# SAMD21.net
KiCad netlist of a schematic drawn in Altium Designer
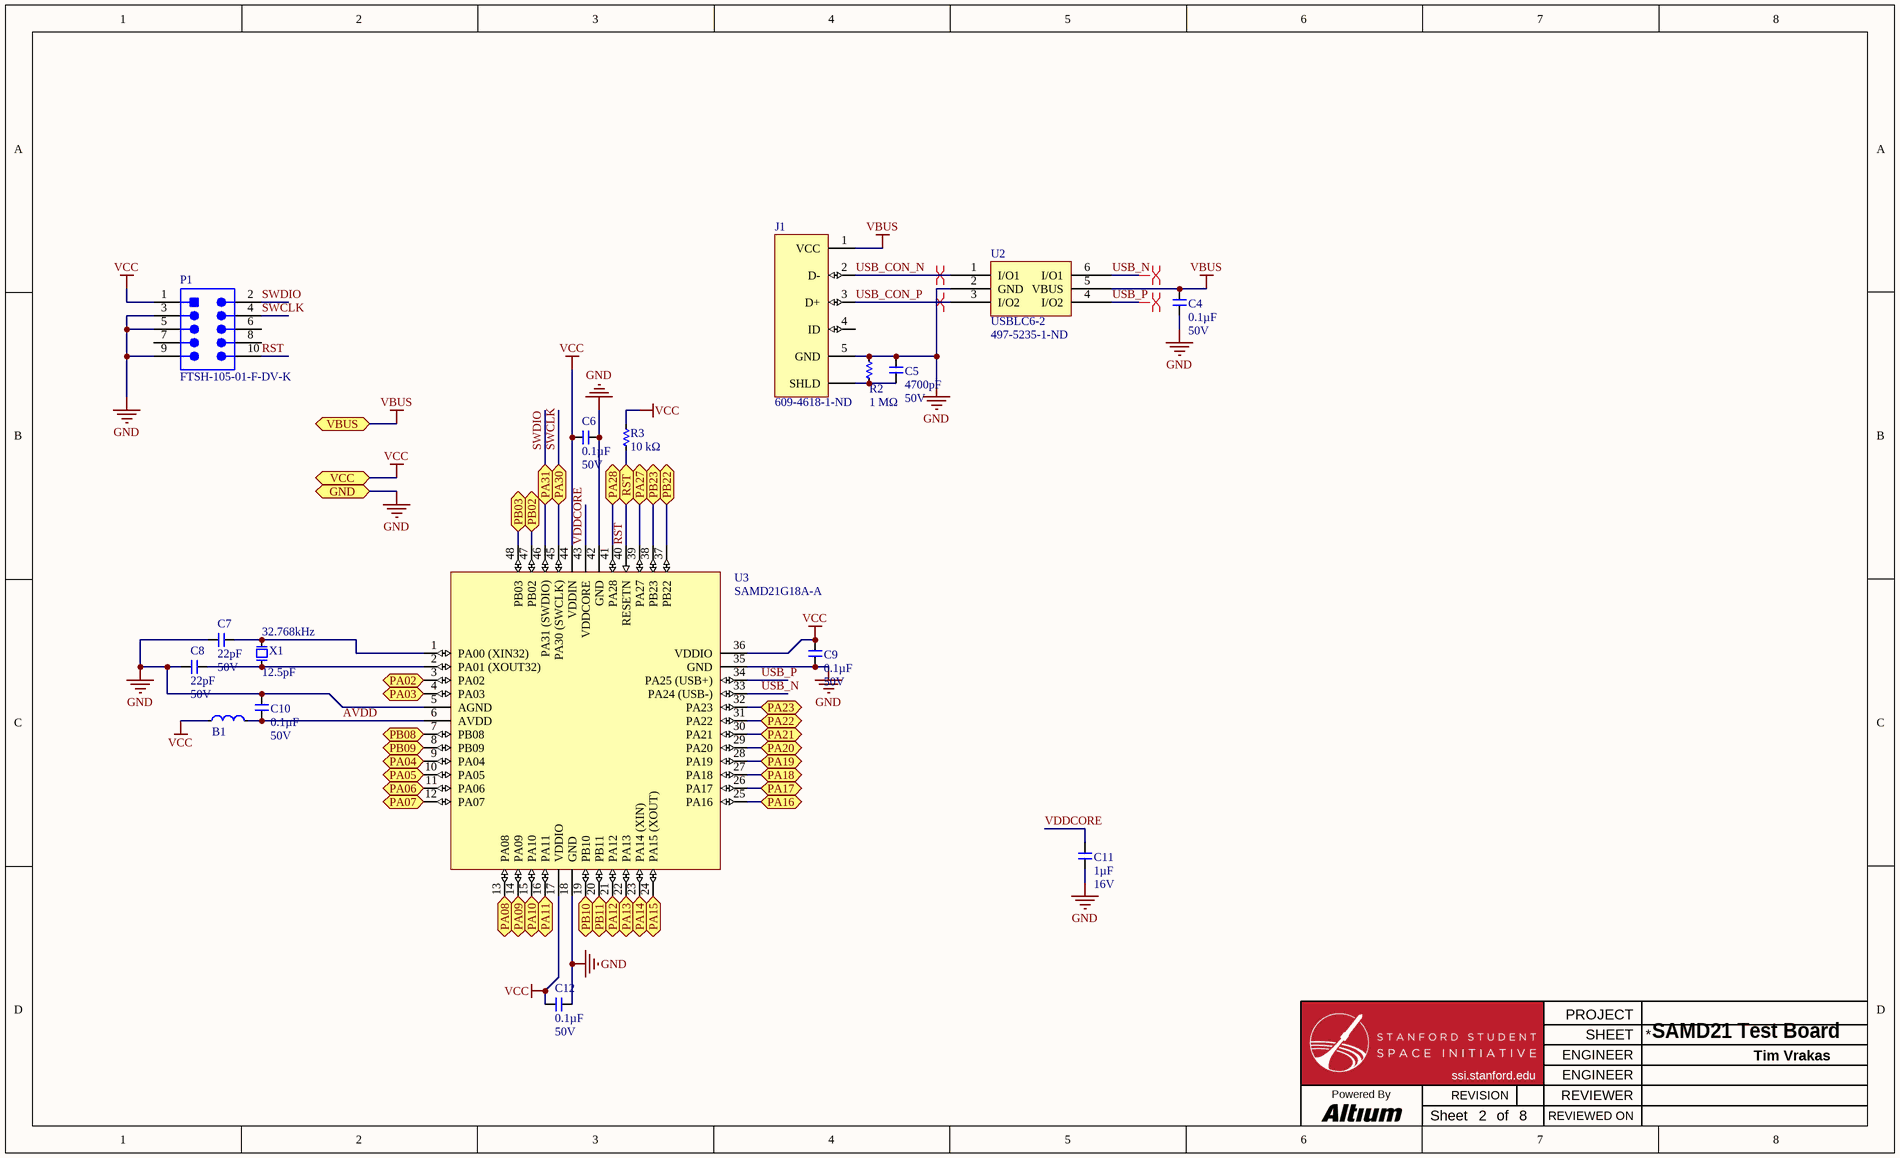
[diagram p0: SAMD21.SchDoc]

(export (version "E")
  (design (tool "Eeschema 10.0.6"))
  (components
    (comp (ref "B1")
      (value "FB_1608")
      (footprint "R0603")
      (description "FERRITE BEAD 600 OHM 300mA")
      (fields
        (field (name "MANUFACTURER") "Taiyo Yuden")
        (field (name "MANUFACTURER PART NUMBER") "BK1608HW601-T")
      )
      (libsource (lib "SSI") (part "FB_1608"))
    )
    (comp (ref "C4")
      (value "__template_cap")
      (footprint "C0603")
      (description "CAP CER 0603 0.1µF X7R 50V 10%")
      (fields
        (field (name "CAPACITANCE (SHORTHAND)") "0.1µF")
        (field (name "RATED VOLTAGE") "50V")
        (field (name "MANUFACTURER") "Murata Electronics North America")
      )
      (libsource (lib "passives") (part "__template_cap"))
    )
    (comp (ref "C5")
      (value "__template_cap")
      (footprint "C0603")
      (description "CAP CER 0603 4700pF X7R 50V 10%")
      (fields
        (field (name "CAPACITANCE (SHORTHAND)") "4700pF")
        (field (name "RATED VOLTAGE") "50V")
        (field (name "MANUFACTURER") "Murata Electronics North America")
      )
      (libsource (lib "passives") (part "__template_cap"))
    )
    (comp (ref "C6")
      (value "__template_cap")
      (footprint "C0603")
      (description "CAP CER 0603 0.1µF X7R 50V 10%")
      (fields
        (field (name "CAPACITANCE (SHORTHAND)") "0.1µF")
        (field (name "RATED VOLTAGE") "50V")
        (field (name "MANUFACTURER") "Murata Electronics North America")
      )
      (libsource (lib "passives") (part "__template_cap"))
    )
    (comp (ref "C7")
      (value "__template_cap")
      (footprint "C0603")
      (description "CAP CER 22PF 50V C0G/NP0 0603")
      (fields
        (field (name "CAPACITANCE (SHORTHAND)") "22pF")
        (field (name "RATED VOLTAGE") "50V")
        (field (name "MANUFACTURER") "Murata Electronics North America")
      )
      (libsource (lib "passives") (part "__template_cap"))
    )
    (comp (ref "C8")
      (value "__template_cap")
      (footprint "C0603")
      (description "CAP CER 22PF 50V C0G/NP0 0603")
      (fields
        (field (name "CAPACITANCE (SHORTHAND)") "22pF")
        (field (name "RATED VOLTAGE") "50V")
        (field (name "MANUFACTURER") "Murata Electronics North America")
      )
      (libsource (lib "passives") (part "__template_cap"))
    )
    (comp (ref "C9")
      (value "__template_cap")
      (footprint "C0603")
      (description "CAP CER 0603 0.1µF X7R 50V 10%")
      (fields
        (field (name "CAPACITANCE (SHORTHAND)") "0.1µF")
        (field (name "RATED VOLTAGE") "50V")
        (field (name "MANUFACTURER") "Murata Electronics North America")
      )
      (libsource (lib "passives") (part "__template_cap"))
    )
    (comp (ref "C10")
      (value "__template_cap")
      (footprint "C0603")
      (description "CAP CER 0603 0.1µF X7R 50V 10%")
      (fields
        (field (name "CAPACITANCE (SHORTHAND)") "0.1µF")
        (field (name "RATED VOLTAGE") "50V")
        (field (name "MANUFACTURER") "Murata Electronics North America")
      )
      (libsource (lib "passives") (part "__template_cap"))
    )
    (comp (ref "C11")
      (value "__template_cap")
      (footprint "C0603")
      (description "CAP CER 0603 1µF X7R 16V 10%")
      (fields
        (field (name "CAPACITANCE (SHORTHAND)") "1µF")
        (field (name "RATED VOLTAGE") "16V")
        (field (name "MANUFACTURER") "Murata Electronics North America")
      )
      (libsource (lib "passives") (part "__template_cap"))
    )
    (comp (ref "C12")
      (value "__template_cap")
      (footprint "C0603")
      (description "CAP CER 0603 0.1µF X7R 50V 10%")
      (fields
        (field (name "CAPACITANCE (SHORTHAND)") "0.1µF")
        (field (name "RATED VOLTAGE") "50V")
        (field (name "MANUFACTURER") "Murata Electronics North America")
      )
      (libsource (lib "passives") (part "__template_cap"))
    )
    (comp (ref "J1")
      (value "CONN_USB_MICROB_SMD_TH_R/A")
      (footprint "CONN_USBMICROB_10118194-0001LF")
      (description "CONN RCPT USB2.0 MICRO B SMD R/A")
      (fields
        (field (name "MANUFACTURER") "Amphenol FCI")
        (field (name "MANUFACTURER PART NUMBER") "10118194-0001LF")
        (field (name "SUPPLIER PART NUMBER 1") "609-4618-1-ND")
      )
      (libsource (lib "SSI") (part "CONN_USB_MICROB_SMD_TH_R/A"))
    )
    (comp (ref "P1")
      (value "FTSH-105-01-F-DV-K")
      (footprint "SMTC-FTSH-105-01-L-DV-K_V")
      (description "Male Header, Pitch 1.27 mm, 2 x 5 Position, Height 6.12 mm, RoHS, Tube")
      (fields (field (name "MANUFACTURER") "Samtec"))
      (libsource (lib "Altium Content Vault") (part "CN-2P-M-R10"))
    )
    (comp (ref "R2")
      (value "__template_resistor")
      (footprint "R0603")
      (description "RES SMD 1M OHM 1% 1/10W 0603")
      (fields
        (field (name "RESISTANCE") "1 MΩ")
        (field (name "MANUFACTURER PART NUMBER") "RC0603FR-071ML")
        (field (name "MANUFACTURER") "Yageo")
      )
      (libsource (lib "passives") (part "__template_resistor"))
    )
    (comp (ref "R3")
      (value "__template_resistor")
      (footprint "R0603")
      (description "RES SMD 10K OHM 1% 1/10W 0603")
      (fields
        (field (name "RESISTANCE") "10 kΩ")
        (field (name "MANUFACTURER PART NUMBER") "RC0603FR-0710KL")
        (field (name "MANUFACTURER") "Yageo")
      )
      (libsource (lib "passives") (part "__template_resistor"))
    )
    (comp (ref "U2")
      (value "USBLC6-2")
      (footprint "6SOT23")
      (fields
        (field (name "MANUFACTURER") "STMicroelectronics")
        (field (name "MANUFACTURER PART NUMBER") "USBLC6-2SC6")
        (field (name "SUPPLIER PART NUMBER 1") "497-5235-1-ND")
      )
      (libsource (lib "SSI") (part "USBLC6-2"))
    )
    (comp (ref "U3")
      (value "SAMD21G18A-A")
      (footprint "SAMD21 TQFP-48")
      (description "48Mhz Atmel SAM ARM Cortex M0+")
      (libsource (lib "SSI") (part "SAMD21G18A-A"))
    )
    (comp (ref "X1")
      (value "XTAL_9HT10-32.768KEZF-T")
      (footprint "XTAL_TXC_9HT10")
      (description "CRYSTAL 32.768 KHZ 12.5 PF SMD")
      (fields
        (field (name "MANUFACTURER") "TXC CORPORATION")
        (field (name "MANUFACTURER PART NUMBER") "9HT10-32.768KEZF-T")
        (field (name "FREQUENCY") "32.768kHz")
        (field (name "LOAD CAPACITANCE") "12.5pF")
      )
      (libsource (lib "SSI") (part "XTAL_9HT10-32.768KEZF-T"))
    )
  )
  (nets
    (net (code "1") (name "/AVDD") (class "Default")
      (node (ref "B1") (pin "2") (pinfunction "2_2") (pintype "passive"))
      (node (ref "C10") (pin "2") (pintype "passive"))
      (node (ref "U3") (pin "6") (pinfunction "AVDD_6") (pintype "power_in"))
    )
    (net (code "2") (name "/PA02") (class "Default")
      (node (ref "U3") (pin "3") (pinfunction "PA02_3") (pintype "bidirectional"))
    )
    (net (code "3") (name "/PA03") (class "Default")
      (node (ref "U3") (pin "4") (pinfunction "PA03_4") (pintype "bidirectional"))
    )
    (net (code "4") (name "/PA04") (class "Default")
      (node (ref "U3") (pin "9") (pinfunction "PA04_9") (pintype "bidirectional"))
    )
    (net (code "5") (name "/PA05") (class "Default")
      (node (ref "U3") (pin "10") (pinfunction "PA05_10") (pintype "bidirectional"))
    )
    (net (code "6") (name "/PA06") (class "Default")
      (node (ref "U3") (pin "11") (pinfunction "PA06_11") (pintype "bidirectional"))
    )
    (net (code "7") (name "/PA07") (class "Default")
      (node (ref "U3") (pin "12") (pinfunction "PA07_12") (pintype "bidirectional"))
    )
    (net (code "8") (name "/PA08") (class "Default")
      (node (ref "U3") (pin "13") (pinfunction "PA08_13") (pintype "bidirectional"))
    )
    (net (code "9") (name "/PA09") (class "Default")
      (node (ref "U3") (pin "14") (pinfunction "PA09_14") (pintype "bidirectional"))
    )
    (net (code "10") (name "/PA10") (class "Default")
      (node (ref "U3") (pin "15") (pinfunction "PA10_15") (pintype "bidirectional"))
    )
    (net (code "11") (name "/PA11") (class "Default")
      (node (ref "U3") (pin "16") (pinfunction "PA11_16") (pintype "bidirectional"))
    )
    (net (code "12") (name "/PA12") (class "Default")
      (node (ref "U3") (pin "21") (pinfunction "PA12_21") (pintype "bidirectional"))
    )
    (net (code "13") (name "/PA13") (class "Default")
      (node (ref "U3") (pin "22") (pinfunction "PA13_22") (pintype "bidirectional"))
    )
    (net (code "14") (name "/PA14") (class "Default")
      (node (ref "U3") (pin "23") (pinfunction "PA14_(XIN)_23") (pintype "bidirectional"))
    )
    (net (code "15") (name "/PA15") (class "Default")
      (node (ref "U3") (pin "24") (pinfunction "PA15_(XOUT)_24") (pintype "bidirectional"))
    )
    (net (code "16") (name "/PA16") (class "Default")
      (node (ref "U3") (pin "25") (pinfunction "PA16_25") (pintype "bidirectional"))
    )
    (net (code "17") (name "/PA17") (class "Default")
      (node (ref "U3") (pin "26") (pinfunction "PA17_26") (pintype "bidirectional"))
    )
    (net (code "18") (name "/PA18") (class "Default")
      (node (ref "U3") (pin "27") (pinfunction "PA18_27") (pintype "bidirectional"))
    )
    (net (code "19") (name "/PA19") (class "Default")
      (node (ref "U3") (pin "28") (pinfunction "PA19_28") (pintype "bidirectional"))
    )
    (net (code "20") (name "/PA20") (class "Default")
      (node (ref "U3") (pin "29") (pinfunction "PA20_29") (pintype "bidirectional"))
    )
    (net (code "21") (name "/PA21") (class "Default")
      (node (ref "U3") (pin "30") (pinfunction "PA21_30") (pintype "bidirectional"))
    )
    (net (code "22") (name "/PA22") (class "Default")
      (node (ref "U3") (pin "31") (pinfunction "PA22_31") (pintype "bidirectional"))
    )
    (net (code "23") (name "/PA23") (class "Default")
      (node (ref "U3") (pin "32") (pinfunction "PA23_32") (pintype "bidirectional"))
    )
    (net (code "24") (name "/PA27") (class "Default")
      (node (ref "U3") (pin "39") (pinfunction "PA27_39") (pintype "bidirectional"))
    )
    (net (code "25") (name "/PA28") (class "Default")
      (node (ref "U3") (pin "41") (pinfunction "PA28_41") (pintype "bidirectional"))
    )
    (net (code "26") (name "/PB02") (class "Default")
      (node (ref "U3") (pin "47") (pinfunction "PB02_47") (pintype "bidirectional"))
    )
    (net (code "27") (name "/PB03") (class "Default")
      (node (ref "U3") (pin "48") (pinfunction "PB03_48") (pintype "bidirectional"))
    )
    (net (code "28") (name "/PB08") (class "Default")
      (node (ref "U3") (pin "7") (pinfunction "PB08_7") (pintype "bidirectional"))
    )
    (net (code "29") (name "/PB09") (class "Default")
      (node (ref "U3") (pin "8") (pinfunction "PB09_8") (pintype "bidirectional"))
    )
    (net (code "30") (name "/PB10") (class "Default")
      (node (ref "U3") (pin "19") (pinfunction "PB10_19") (pintype "bidirectional"))
    )
    (net (code "31") (name "/PB11") (class "Default")
      (node (ref "U3") (pin "20") (pinfunction "PB11_20") (pintype "bidirectional"))
    )
    (net (code "32") (name "/PB22") (class "Default")
      (node (ref "U3") (pin "37") (pinfunction "PB22_37") (pintype "bidirectional"))
    )
    (net (code "33") (name "/PB23") (class "Default")
      (node (ref "U3") (pin "38") (pinfunction "PB23_38") (pintype "bidirectional"))
    )
    (net (code "34") (name "/RST") (class "Default")
      (node (ref "P1") (pin "10") (pinfunction "10_10") (pintype "passive"))
      (node (ref "R3") (pin "1") (pintype "passive"))
      (node (ref "U3") (pin "40") (pinfunction "RESETN_40") (pintype "input"))
    )
    (net (code "35") (name "/SWCLK") (class "Default")
      (node (ref "P1") (pin "4") (pinfunction "4_4") (pintype "passive"))
      (node (ref "U3") (pin "45") (pinfunction "PA30_(SWCLK)_45") (pintype "bidirectional"))
    )
    (net (code "36") (name "/SWDIO") (class "Default")
      (node (ref "P1") (pin "2") (pinfunction "2_2") (pintype "passive"))
      (node (ref "U3") (pin "46") (pinfunction "PA31_(SWDIO)_46") (pintype "bidirectional"))
    )
    (net (code "37") (name "/USB_CON_N") (class "Default")
      (node (ref "J1") (pin "2") (pinfunction "D-_2") (pintype "bidirectional"))
      (node (ref "U2") (pin "1") (pinfunction "I/O1_1") (pintype "passive"))
    )
    (net (code "38") (name "/USB_CON_P") (class "Default")
      (node (ref "J1") (pin "3") (pinfunction "D+_3") (pintype "bidirectional"))
      (node (ref "U2") (pin "3") (pinfunction "I/O2_3") (pintype "passive"))
    )
    (net (code "39") (name "/USB_N") (class "Default")
      (node (ref "U2") (pin "6") (pinfunction "I/O1_6") (pintype "passive"))
      (node (ref "U3") (pin "33") (pinfunction "PA24_(USB-)_33") (pintype "bidirectional"))
    )
    (net (code "40") (name "/USB_P") (class "Default")
      (node (ref "U2") (pin "4") (pinfunction "I/O2_4") (pintype "passive"))
      (node (ref "U3") (pin "34") (pinfunction "PA25_(USB+)_34") (pintype "bidirectional"))
    )
    (net (code "41") (name "/VDDCORE") (class "Default")
      (node (ref "C11") (pin "1") (pintype "passive"))
      (node (ref "U3") (pin "43") (pinfunction "VDDCORE_43") (pintype "power_in"))
    )
    (net (code "42") (name "GND") (class "Default")
      (node (ref "C10") (pin "1") (pintype "passive"))
      (node (ref "C11") (pin "2") (pintype "passive"))
      (node (ref "C12") (pin "2") (pintype "passive"))
      (node (ref "C4") (pin "2") (pintype "passive"))
      (node (ref "C5") (pin "1") (pintype "passive"))
      (node (ref "C6") (pin "2") (pintype "passive"))
      (node (ref "C7") (pin "1") (pintype "passive"))
      (node (ref "C8") (pin "1") (pintype "passive"))
      (node (ref "C9") (pin "2") (pintype "passive"))
      (node (ref "J1") (pin "5") (pinfunction "GND_5") (pintype "power_in"))
      (node (ref "P1") (pin "3") (pinfunction "3_3") (pintype "passive"))
      (node (ref "P1") (pin "5") (pinfunction "5_5") (pintype "passive"))
      (node (ref "P1") (pin "9") (pinfunction "9_9") (pintype "passive"))
      (node (ref "R2") (pin "2") (pintype "passive"))
      (node (ref "U2") (pin "2") (pinfunction "GND_2") (pintype "passive"))
      (node (ref "U3") (pin "18") (pinfunction "GND_18") (pintype "power_in"))
      (node (ref "U3") (pin "35") (pinfunction "GND_35") (pintype "power_in"))
      (node (ref "U3") (pin "42") (pinfunction "GND_42") (pintype "power_in"))
      (node (ref "U3") (pin "5") (pinfunction "AGND_5") (pintype "power_in"))
    )
    (net (code "43") (name "Net-(J1-SHLD)") (class "Default")
      (node (ref "C5") (pin "2") (pintype "passive"))
      (node (ref "J1") (pin "SHIELD") (pinfunction "SHLD_SHIELD") (pintype "power_in"))
      (node (ref "R2") (pin "1") (pintype "passive"))
    )
    (net (code "44") (name "Net-(U3-PA00_(XIN32))") (class "Default")
      (node (ref "C7") (pin "2") (pintype "passive"))
      (node (ref "U3") (pin "1") (pinfunction "PA00_(XIN32)_1") (pintype "bidirectional"))
      (node (ref "X1") (pin "2") (pinfunction "2_2") (pintype "passive"))
    )
    (net (code "45") (name "Net-(U3-PA01_(XOUT32))") (class "Default")
      (node (ref "C8") (pin "2") (pintype "passive"))
      (node (ref "U3") (pin "2") (pinfunction "PA01_(XOUT32)_2") (pintype "bidirectional"))
      (node (ref "X1") (pin "1") (pinfunction "1_1") (pintype "passive"))
    )
    (net (code "46") (name "VBUS") (class "Default")
      (node (ref "C4") (pin "1") (pintype "passive"))
      (node (ref "J1") (pin "1") (pinfunction "VCC_1") (pintype "power_in"))
      (node (ref "U2") (pin "5") (pinfunction "VBUS_5") (pintype "passive"))
    )
    (net (code "47") (name "VCC") (class "Default")
      (node (ref "B1") (pin "1") (pinfunction "1_1") (pintype "passive"))
      (node (ref "C12") (pin "1") (pintype "passive"))
      (node (ref "C6") (pin "1") (pintype "passive"))
      (node (ref "C9") (pin "1") (pintype "passive"))
      (node (ref "P1") (pin "1") (pinfunction "1_1") (pintype "passive"))
      (node (ref "R3") (pin "2") (pintype "passive"))
      (node (ref "U3") (pin "17") (pinfunction "VDDIO_17") (pintype "power_in"))
      (node (ref "U3") (pin "36") (pinfunction "VDDIO_36") (pintype "power_in"))
      (node (ref "U3") (pin "44") (pinfunction "VDDIN_44") (pintype "power_in"))
    )
    (net (code "48") (name "unconnected-(J1-ID-Pad4)") (class "Default")
      (node (ref "J1") (pin "4") (pinfunction "ID_4") (pintype "bidirectional"))
    )
    (net (code "49") (name "unconnected-(P1-Pad6)") (class "Default")
      (node (ref "P1") (pin "6") (pinfunction "6_6") (pintype "passive"))
    )
    (net (code "50") (name "unconnected-(P1-Pad7)") (class "Default")
      (node (ref "P1") (pin "7") (pinfunction "7_7") (pintype "passive"))
    )
    (net (code "51") (name "unconnected-(P1-Pad8)") (class "Default")
      (node (ref "P1") (pin "8") (pinfunction "8_8") (pintype "passive"))
    )
  )
)
